# micro_sd_breakout.net
KiCad netlist of a schematic drawn in EAGLE
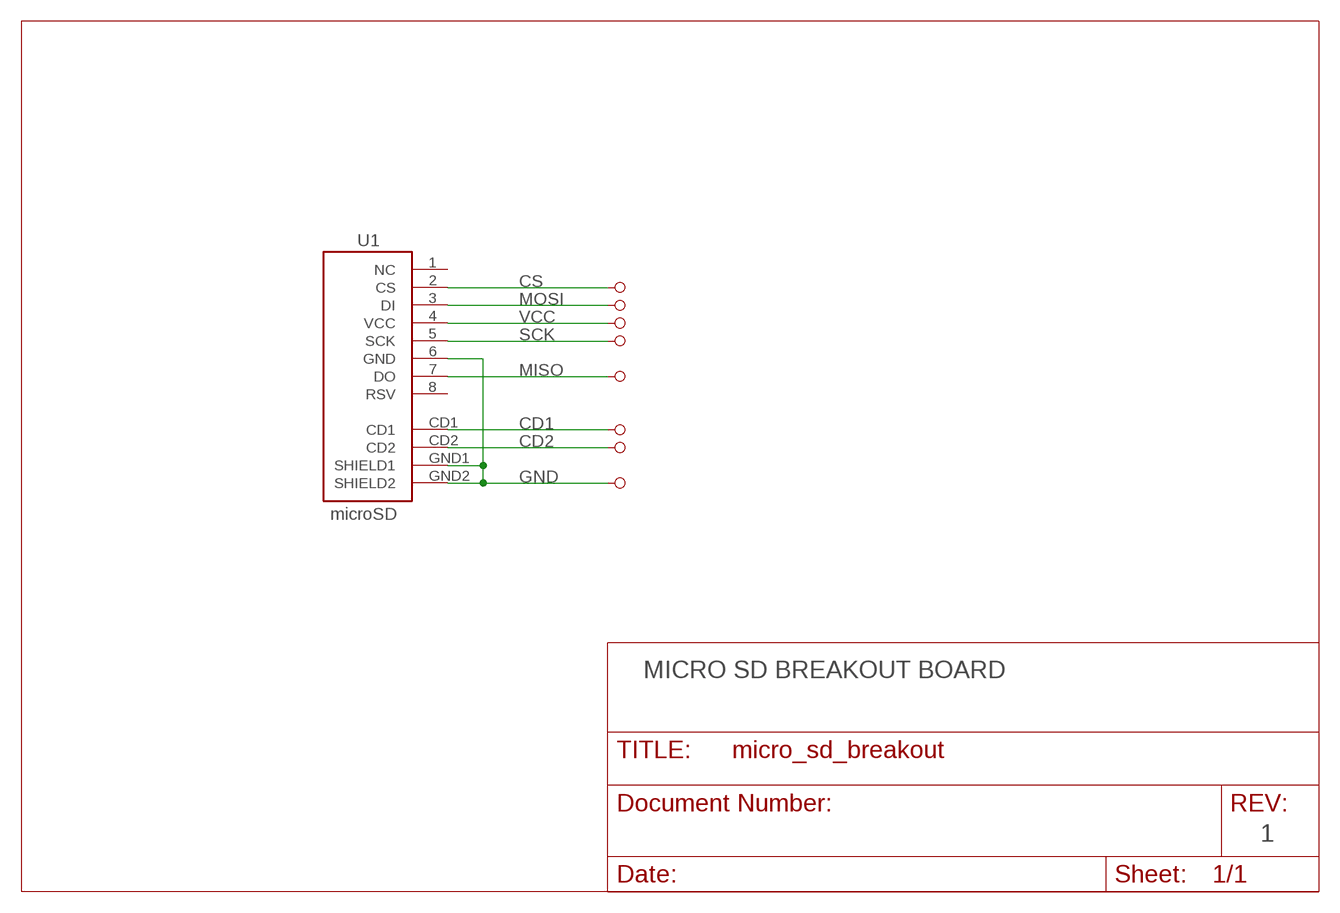
[diagram p0: schematic, sheet 1]

(export (version "E")
  (design (tool "Eeschema 10.0.6"))
  (components
    (comp (ref "JP1")
      (value "PINHD-1X1")
      (footprint "eagle-import:1X01")
      (libsource (lib "eagle-import") (part "PINHD-1X1"))
    )
    (comp (ref "JP2")
      (value "PINHD-1X1")
      (footprint "eagle-import:1X01")
      (libsource (lib "eagle-import") (part "PINHD-1X1"))
    )
    (comp (ref "JP3")
      (value "PINHD-1X1")
      (footprint "eagle-import:1X01")
      (libsource (lib "eagle-import") (part "PINHD-1X1"))
    )
    (comp (ref "JP4")
      (value "PINHD-1X1")
      (footprint "eagle-import:1X01")
      (libsource (lib "eagle-import") (part "PINHD-1X1"))
    )
    (comp (ref "JP5")
      (value "PINHD-1X1")
      (footprint "eagle-import:1X01")
      (libsource (lib "eagle-import") (part "PINHD-1X1"))
    )
    (comp (ref "JP6")
      (value "PINHD-1X1")
      (footprint "eagle-import:1X01")
      (libsource (lib "eagle-import") (part "PINHD-1X1"))
    )
    (comp (ref "JP7")
      (value "PINHD-1X1")
      (footprint "eagle-import:1X01")
      (libsource (lib "eagle-import") (part "PINHD-1X1"))
    )
    (comp (ref "JP8")
      (value "PINHD-1X1")
      (footprint "eagle-import:1X01")
      (libsource (lib "eagle-import") (part "PINHD-1X1"))
    )
    (comp (ref "U1")
      (value "microSD")
      (footprint "eagle-import:MICRO-SD-SOCKET-PP")
      (libsource (lib "eagle-import") (part "USD-SOCKETSMD"))
    )
  )
  (nets
    (net (code "1") (name "/CD1") (class "Default")
      (node (ref "JP6") (pin "1") (pinfunction "1_1") (pintype "passive"))
      (node (ref "U1") (pin "CD1") (pinfunction "CD1_CD1") (pintype "bidirectional"))
    )
    (net (code "2") (name "/CD2") (class "Default")
      (node (ref "JP7") (pin "1") (pinfunction "1_1") (pintype "passive"))
      (node (ref "U1") (pin "CD2") (pinfunction "CD2_CD2") (pintype "bidirectional"))
    )
    (net (code "3") (name "/CS") (class "Default")
      (node (ref "JP1") (pin "1") (pinfunction "1_1") (pintype "passive"))
      (node (ref "U1") (pin "2") (pinfunction "CS_2") (pintype "bidirectional"))
    )
    (net (code "4") (name "/GND") (class "Default")
      (node (ref "JP8") (pin "1") (pinfunction "1_1") (pintype "passive"))
      (node (ref "U1") (pin "6") (pinfunction "GND_6") (pintype "bidirectional"))
      (node (ref "U1") (pin "GND1") (pinfunction "SHIELD1_GND1") (pintype "bidirectional"))
      (node (ref "U1") (pin "GND2") (pinfunction "SHIELD2_GND2") (pintype "bidirectional"))
    )
    (net (code "5") (name "/MISO") (class "Default")
      (node (ref "JP5") (pin "1") (pinfunction "1_1") (pintype "passive"))
      (node (ref "U1") (pin "7") (pinfunction "DO_7") (pintype "bidirectional"))
    )
    (net (code "6") (name "/MOSI") (class "Default")
      (node (ref "JP2") (pin "1") (pinfunction "1_1") (pintype "passive"))
      (node (ref "U1") (pin "3") (pinfunction "DI_3") (pintype "bidirectional"))
    )
    (net (code "7") (name "/SCK") (class "Default")
      (node (ref "JP4") (pin "1") (pinfunction "1_1") (pintype "passive"))
      (node (ref "U1") (pin "5") (pinfunction "SCK_5") (pintype "bidirectional"))
    )
    (net (code "8") (name "/VCC") (class "Default")
      (node (ref "JP3") (pin "1") (pinfunction "1_1") (pintype "passive"))
      (node (ref "U1") (pin "4") (pinfunction "VCC_4") (pintype "bidirectional"))
    )
    (net (code "9") (name "unconnected-(U1-NC-Pad1)") (class "Default")
      (node (ref "U1") (pin "1") (pinfunction "NC_1") (pintype "bidirectional"))
    )
    (net (code "10") (name "unconnected-(U1-RSV-Pad8)") (class "Default")
      (node (ref "U1") (pin "8") (pinfunction "RSV_8") (pintype "bidirectional"))
    )
  )
)
